# Stepper.net
KiCad netlist of a schematic drawn in Altium Designer
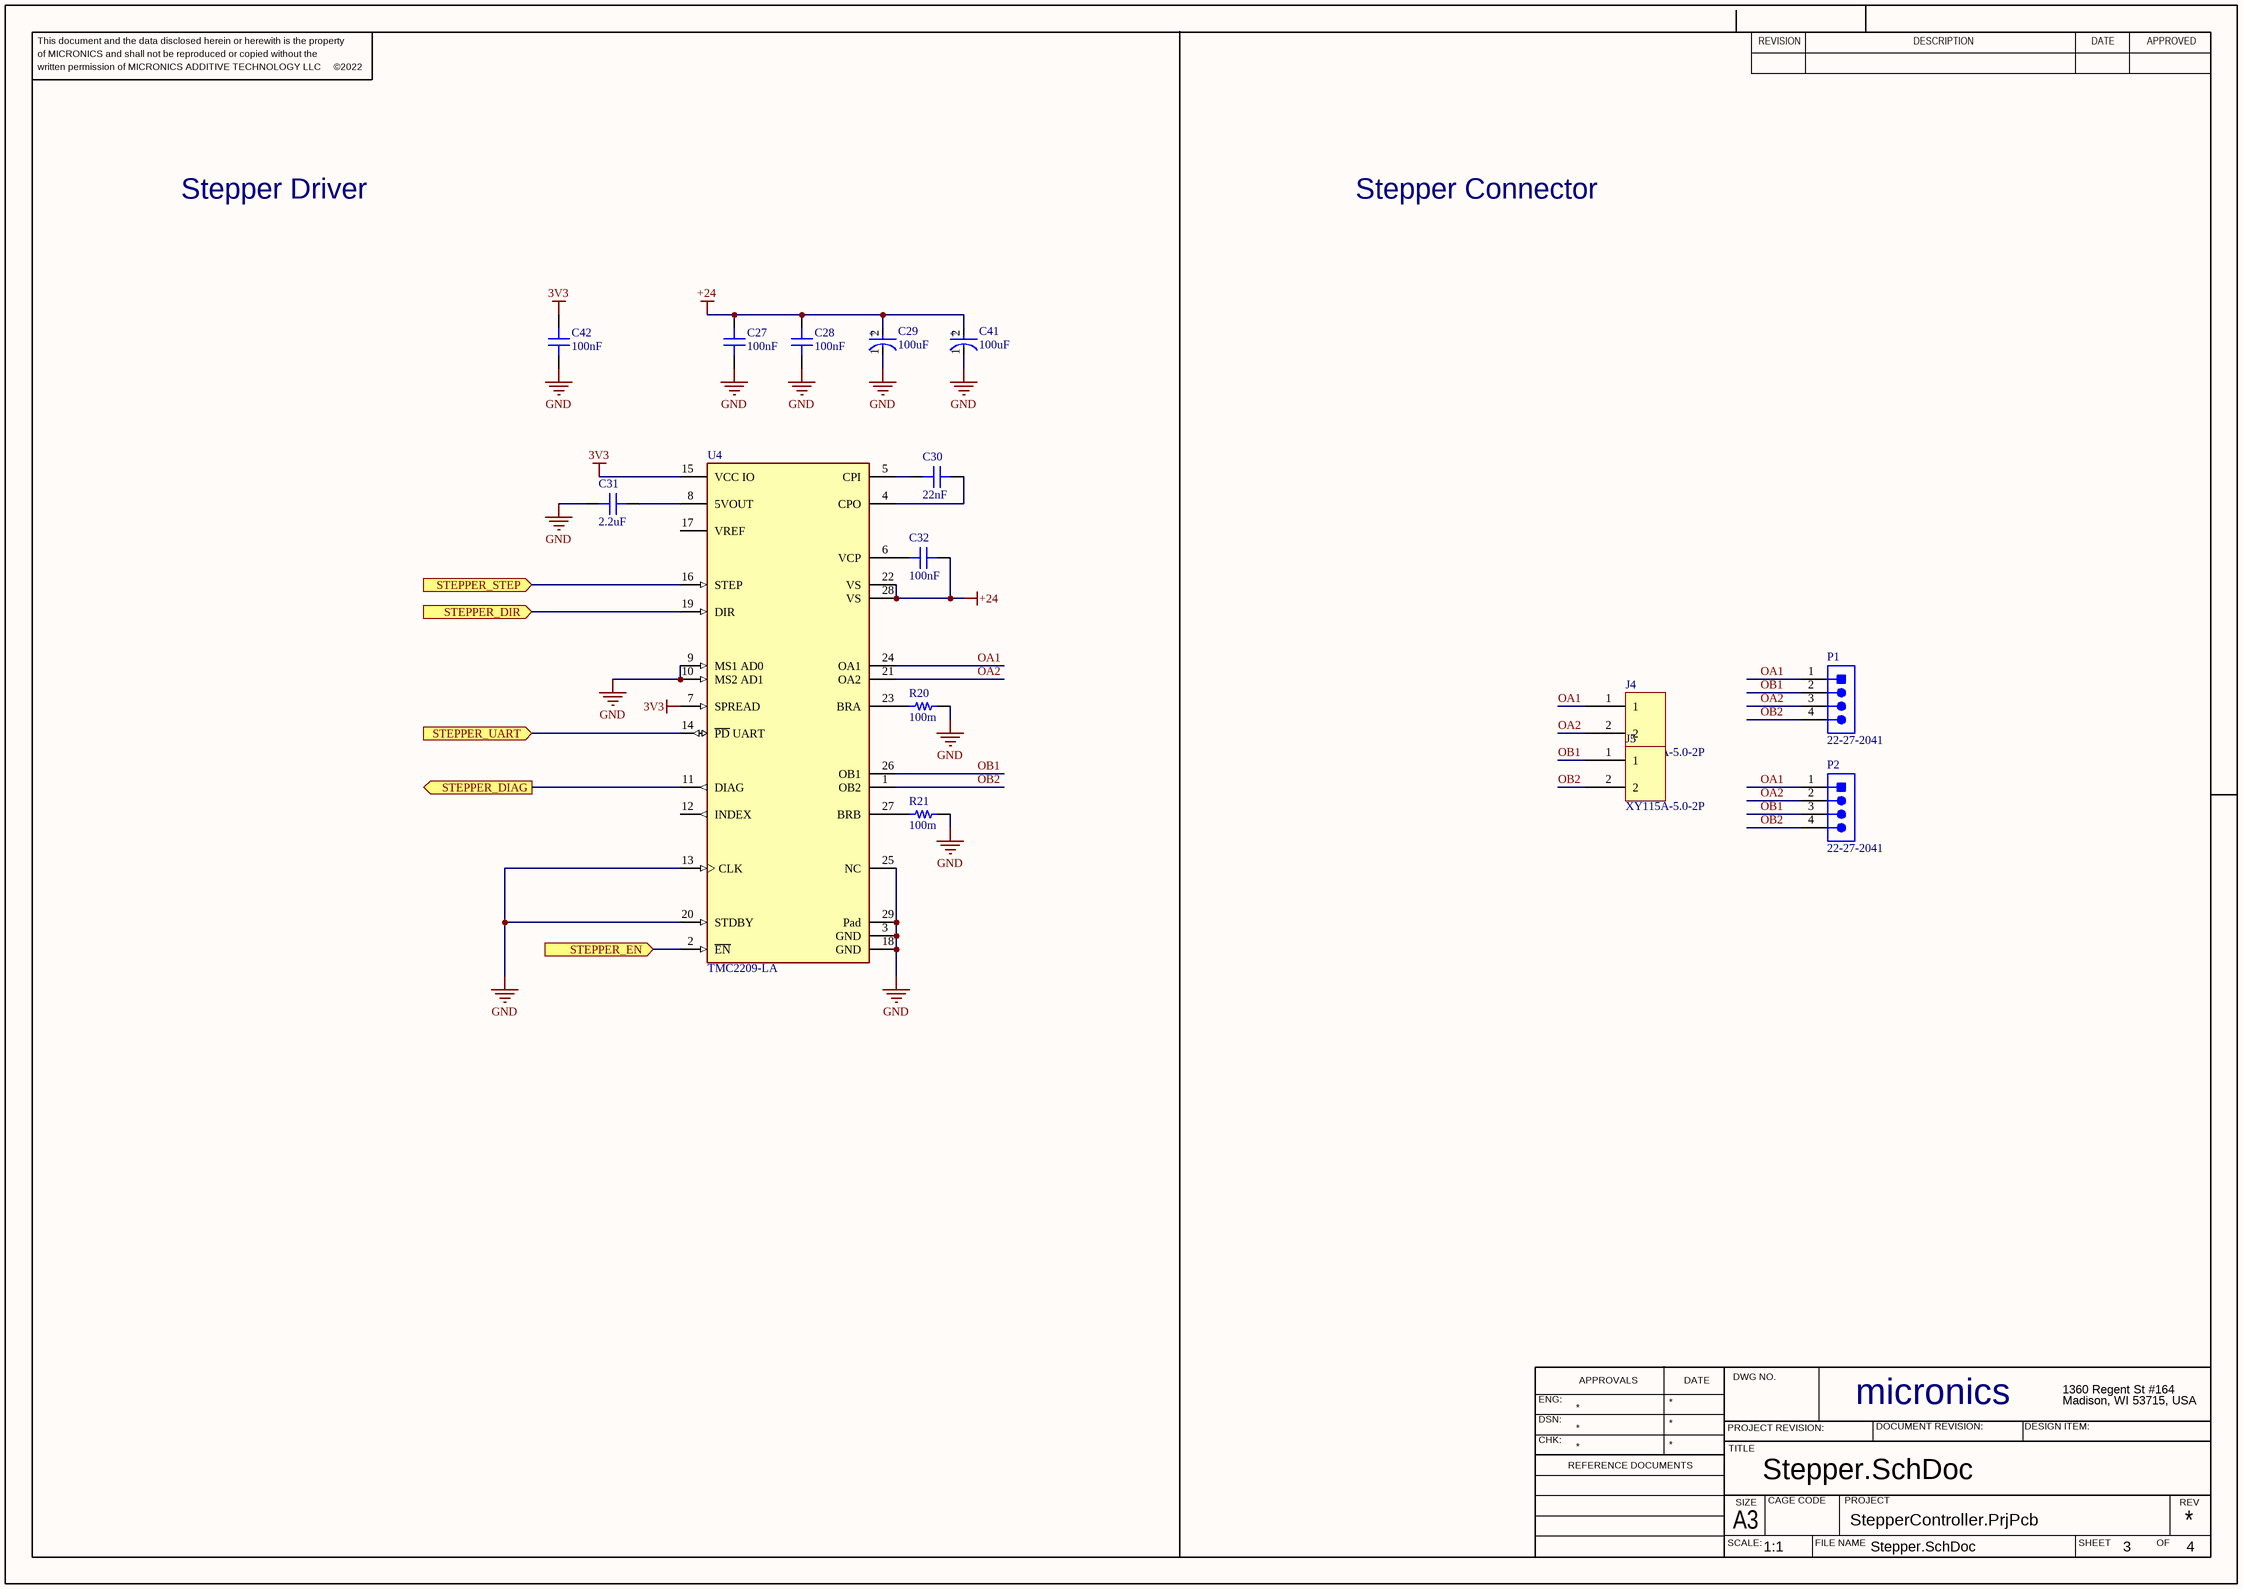
[diagram p0: Stepper.SchDoc]

(export (version "E")
  (design (tool "Eeschema 10.0.6"))
  (components
    (comp (ref "C27")
      (value "100nF")
      (footprint "CAP 0603_1608")
      (description "C14663")
      (fields
        (field (name "PART NUMBER") "250X14W223MV4T")
        (field (name "MANUFACTURER") "Johanson Dielectrics Inc.")
      )
      (libsource (lib "Celestial Altium Library - altium_library") (part "Capacitor"))
    )
    (comp (ref "C28")
      (value "100nF")
      (footprint "CAP 0603_1608")
      (description "C14663")
      (fields
        (field (name "PART NUMBER") "250X14W223MV4T")
        (field (name "MANUFACTURER") "Johanson Dielectrics Inc.")
      )
      (libsource (lib "Celestial Altium Library - altium_library") (part "Capacitor"))
    )
    (comp (ref "C29")
      (value "100uF")
      (footprint "FP-SGV8X10_5-MFG")
      (description "C445063")
      (fields (field (name "VOLTAGE") "50V") (field (name "TOLERANCE") "20%"))
      (libsource (lib "Altium Content Vault") (part "203bc49f2ac43e59fd269a8c329ed05"))
    )
    (comp (ref "C30")
      (value "22nF")
      (footprint "CAP 0603_1608")
      (description "C21122")
      (fields
        (field (name "PART NUMBER") "250X14W223MV4T")
        (field (name "MANUFACTURER") "Johanson Dielectrics Inc.")
      )
      (libsource (lib "Celestial Altium Library - altium_library") (part "Capacitor"))
    )
    (comp (ref "C31")
      (value "2.2uF")
      (footprint "CAP 0603_1608")
      (description "C23630")
      (fields
        (field (name "PART NUMBER") "250X14W223MV4T")
        (field (name "MANUFACTURER") "Johanson Dielectrics Inc.")
      )
      (libsource (lib "Celestial Altium Library - altium_library") (part "Capacitor"))
    )
    (comp (ref "C32")
      (value "100nF")
      (footprint "CAP 0603_1608")
      (description "C14663")
      (fields
        (field (name "PART NUMBER") "250X14W223MV4T")
        (field (name "MANUFACTURER") "Johanson Dielectrics Inc.")
      )
      (libsource (lib "Celestial Altium Library - altium_library") (part "Capacitor"))
    )
    (comp (ref "C41")
      (value "100uF")
      (footprint "FP-SGV8X10_5-MFG")
      (description "C445063")
      (fields (field (name "VOLTAGE") "50V") (field (name "TOLERANCE") "20%"))
      (libsource (lib "Altium Content Vault") (part "203bc49f2ac43e59fd269a8c329ed05"))
    )
    (comp (ref "C42")
      (value "100nF")
      (footprint "CAP 0603_1608")
      (description "C14663")
      (fields
        (field (name "PART NUMBER") "250X14W223MV4T")
        (field (name "MANUFACTURER") "Johanson Dielectrics Inc.")
      )
      (libsource (lib "Celestial Altium Library - altium_library") (part "Capacitor"))
    )
    (comp (ref "J4")
      (value "XY115A-5.0-2P")
      (footprint "2.54-2PLTDK")
      (description "C784935")
      (libsource (lib "MicronV4") (part "2.54-2PLTDK"))
    )
    (comp (ref "J5")
      (value "XY115A-5.0-2P")
      (footprint "2.54-2PLTDK")
      (description "C784935")
      (libsource (lib "MicronV4") (part "2.54-2PLTDK"))
    )
    (comp (ref "P1")
      (value "22-27-2041")
      (footprint "MOLX-22-27-2041_V")
      (description "C504991")
      (fields (field (name "MANUFACTURER") "Molex"))
      (libsource (lib "Altium Content Vault") (part "CN-1P-M-R4"))
    )
    (comp (ref "P2")
      (value "22-27-2041")
      (footprint "MOLX-22-27-2041_V")
      (description "C504991")
      (fields (field (name "MANUFACTURER") "Molex"))
      (libsource (lib "Altium Content Vault") (part "CN-1P-M-R4"))
    )
    (comp (ref "R20")
      (value "100m")
      (footprint "RES 1206_3216")
      (description "C25334")
      (fields (field (name "PART NUMBER") "KRL1632E-M-R012-F-T5") (field (name "MANUFACTURER") "Susumu"))
      (libsource (lib "Celestial Altium Library - altium_library") (part "Resistor"))
    )
    (comp (ref "R21")
      (value "100m")
      (footprint "RES 1206_3216")
      (description "C25334")
      (fields (field (name "PART NUMBER") "KRL1632E-M-R012-F-T5") (field (name "MANUFACTURER") "Susumu"))
      (libsource (lib "Celestial Altium Library - altium_library") (part "Resistor"))
    )
    (comp (ref "U4")
      (value "TMC2209-LA")
      (footprint "FP-TMC2209-LA-IPC_C")
      (description "C465949")
      (fields
        (field (name "MANUFACTURER") "Trinamic")
        (field (name "OCTOPART") "https://octopart.com/tmc2209-la-trinamic-105993617")
      )
      (libsource (lib "Altium Content Vault") (part "7a30eefd0264be3c54b4a2c24074cf3"))
    )
  )
  (nets
    (net (code "1") (name "+24") (class "Default")
      (node (ref "C27") (pin "1") (pinfunction "1_1") (pintype "passive"))
      (node (ref "C28") (pin "1") (pinfunction "1_1") (pintype "passive"))
      (node (ref "C29") (pin "2") (pinfunction "A_2") (pintype "passive"))
      (node (ref "C32") (pin "1") (pinfunction "1_1") (pintype "passive"))
      (node (ref "C41") (pin "2") (pinfunction "A_2") (pintype "passive"))
      (node (ref "U4") (pin "22") (pinfunction "VS_22") (pintype "power_in"))
      (node (ref "U4") (pin "28") (pinfunction "VS_28") (pintype "power_in"))
    )
    (net (code "2") (name "/OA1") (class "Default")
      (node (ref "J4") (pin "1") (pinfunction "1_1") (pintype "passive"))
      (node (ref "P1") (pin "1") (pinfunction "1_1") (pintype "passive"))
      (node (ref "P2") (pin "1") (pinfunction "1_1") (pintype "passive"))
      (node (ref "U4") (pin "24") (pinfunction "OA1_24") (pintype "passive"))
    )
    (net (code "3") (name "/OA2") (class "Default")
      (node (ref "J4") (pin "2") (pinfunction "2_2") (pintype "passive"))
      (node (ref "P1") (pin "3") (pinfunction "3_3") (pintype "passive"))
      (node (ref "P2") (pin "2") (pinfunction "2_2") (pintype "passive"))
      (node (ref "U4") (pin "21") (pinfunction "OA2_21") (pintype "passive"))
    )
    (net (code "4") (name "/OB1") (class "Default")
      (node (ref "J5") (pin "1") (pinfunction "1_1") (pintype "passive"))
      (node (ref "P1") (pin "2") (pinfunction "2_2") (pintype "passive"))
      (node (ref "P2") (pin "3") (pinfunction "3_3") (pintype "passive"))
      (node (ref "U4") (pin "26") (pinfunction "OB1_26") (pintype "passive"))
    )
    (net (code "5") (name "/OB2") (class "Default")
      (node (ref "J5") (pin "2") (pinfunction "2_2") (pintype "passive"))
      (node (ref "P1") (pin "4") (pinfunction "4_4") (pintype "passive"))
      (node (ref "P2") (pin "4") (pinfunction "4_4") (pintype "passive"))
      (node (ref "U4") (pin "1") (pinfunction "OB2_1") (pintype "passive"))
    )
    (net (code "6") (name "/STEPPER_DIAG") (class "Default")
      (node (ref "U4") (pin "11") (pinfunction "DIAG_11") (pintype "output"))
    )
    (net (code "7") (name "/STEPPER_DIR") (class "Default")
      (node (ref "U4") (pin "19") (pinfunction "DIR_19") (pintype "input"))
    )
    (net (code "8") (name "/STEPPER_EN") (class "Default")
      (node (ref "U4") (pin "2") (pinfunction "~{EN}_2") (pintype "input"))
    )
    (net (code "9") (name "/STEPPER_STEP") (class "Default")
      (node (ref "U4") (pin "16") (pinfunction "STEP_16") (pintype "input"))
    )
    (net (code "10") (name "/STEPPER_UART") (class "Default")
      (node (ref "U4") (pin "14") (pinfunction "~{PD}_UART_14") (pintype "bidirectional"))
    )
    (net (code "11") (name "3V3") (class "Default")
      (node (ref "C42") (pin "1") (pinfunction "1_1") (pintype "passive"))
      (node (ref "U4") (pin "15") (pinfunction "VCC_IO_15") (pintype "power_in"))
      (node (ref "U4") (pin "7") (pinfunction "SPREAD_7") (pintype "input"))
    )
    (net (code "12") (name "GND") (class "Default")
      (node (ref "C27") (pin "2") (pinfunction "2_2") (pintype "passive"))
      (node (ref "C28") (pin "2") (pinfunction "2_2") (pintype "passive"))
      (node (ref "C29") (pin "1") (pinfunction "C_1") (pintype "passive"))
      (node (ref "C31") (pin "1") (pinfunction "1_1") (pintype "passive"))
      (node (ref "C41") (pin "1") (pinfunction "C_1") (pintype "passive"))
      (node (ref "C42") (pin "2") (pinfunction "2_2") (pintype "passive"))
      (node (ref "R20") (pin "2") (pinfunction "2_2") (pintype "passive"))
      (node (ref "R21") (pin "2") (pinfunction "2_2") (pintype "passive"))
      (node (ref "U4") (pin "10") (pinfunction "MS2_AD1_10") (pintype "input"))
      (node (ref "U4") (pin "13") (pinfunction "CLK_13") (pintype "input"))
      (node (ref "U4") (pin "18") (pinfunction "GND_18") (pintype "power_in"))
      (node (ref "U4") (pin "20") (pinfunction "STDBY_20") (pintype "input"))
      (node (ref "U4") (pin "25") (pinfunction "NC_25") (pintype "passive"))
      (node (ref "U4") (pin "29") (pinfunction "Pad_29") (pintype "power_in"))
      (node (ref "U4") (pin "3") (pinfunction "GND_3") (pintype "power_in"))
      (node (ref "U4") (pin "9") (pinfunction "MS1_AD0_9") (pintype "input"))
    )
    (net (code "13") (name "Net-(U4-5VOUT)") (class "Default")
      (node (ref "C31") (pin "2") (pinfunction "2_2") (pintype "passive"))
      (node (ref "U4") (pin "8") (pinfunction "5VOUT_8") (pintype "power_in"))
    )
    (net (code "14") (name "Net-(U4-BRA)") (class "Default")
      (node (ref "R20") (pin "1") (pinfunction "1_1") (pintype "passive"))
      (node (ref "U4") (pin "23") (pinfunction "BRA_23") (pintype "passive"))
    )
    (net (code "15") (name "Net-(U4-BRB)") (class "Default")
      (node (ref "R21") (pin "1") (pinfunction "1_1") (pintype "passive"))
      (node (ref "U4") (pin "27") (pinfunction "BRB_27") (pintype "passive"))
    )
    (net (code "16") (name "Net-(U4-CPI)") (class "Default")
      (node (ref "C30") (pin "2") (pinfunction "2_2") (pintype "passive"))
      (node (ref "U4") (pin "5") (pinfunction "CPI_5") (pintype "passive"))
    )
    (net (code "17") (name "Net-(U4-CPO)") (class "Default")
      (node (ref "C30") (pin "1") (pinfunction "1_1") (pintype "passive"))
      (node (ref "U4") (pin "4") (pinfunction "CPO_4") (pintype "passive"))
    )
    (net (code "18") (name "Net-(U4-VCP)") (class "Default")
      (node (ref "C32") (pin "2") (pinfunction "2_2") (pintype "passive"))
      (node (ref "U4") (pin "6") (pinfunction "VCP_6") (pintype "power_in"))
    )
    (net (code "19") (name "unconnected-(U4-INDEX-Pad12)") (class "Default")
      (node (ref "U4") (pin "12") (pinfunction "INDEX_12") (pintype "output"))
    )
    (net (code "20") (name "unconnected-(U4-VREF-Pad17)") (class "Default")
      (node (ref "U4") (pin "17") (pinfunction "VREF_17") (pintype "passive"))
    )
  )
)
